# eDP.net
KiCad netlist of a schematic drawn in Altium Designer
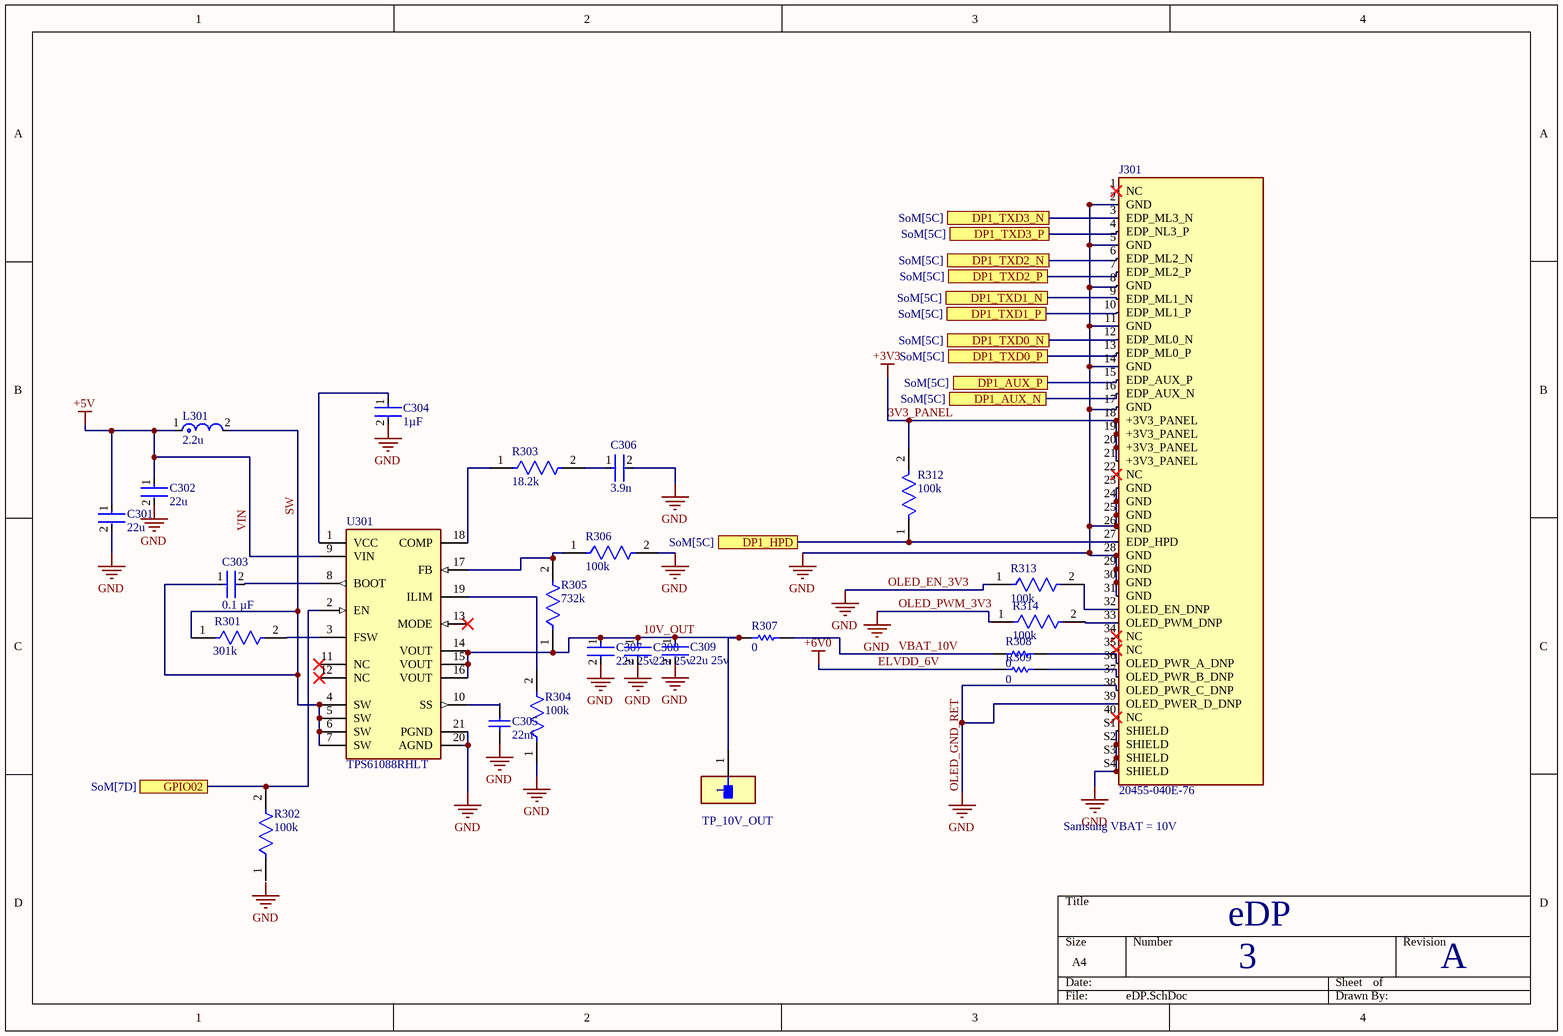
[diagram p0: eDP.SchDoc]

(export (version "E")
  (design (tool "Eeschema 10.0.6"))
  (components
    (comp (ref "C301")
      (value "22u")
      (footprint "FP-CL10-IPC_B")
      (description "Cap Ceramic 22uF 16V X5R ±20% Pad SMD 0603 +85°C T/R")
      (fields (field (name "TOLERANCE") "20%"))
      (libsource (lib "Altium Content Vault") (part "b4654b650e69147ec39a6b967a45e02"))
    )
    (comp (ref "C302")
      (value "22u")
      (footprint "FP-CL10-IPC_B")
      (description "Cap Ceramic 22uF 16V X5R ±20% Pad SMD 0603 +85°C T/R")
      (fields (field (name "TOLERANCE") "20%"))
      (libsource (lib "Altium Content Vault") (part "b4654b650e69147ec39a6b967a45e02"))
    )
    (comp (ref "C303")
      (value "0.1 µF")
      (footprint "FP-GRM155-0_05-IPC_B")
      (description "Chip Multilayer Ceramic Capacitors for General Purpose, 0402, 0.10uF, X7R, 15%, 10%, 50V")
      (fields (field (name "TOLERANCE") "10%"))
      (libsource (lib "Altium Content Vault") (part "02cd4be3c70576c341d710602a673aa"))
    )
    (comp (ref "C304")
      (value "1µF")
      (footprint "FP-GRM15-0_1-MFG")
      (description "CAP CER 1UF 10V X5R 0402")
      (fields
        (field (name "OCTOPART") "https://octopart.com/grm155r61a105ke15d-murata-197442")
        (field (name "MANUFACTURER PART NUMBER") "GRM155R61A105KE15D")
      )
      (libsource (lib "Altium Content Vault") (part "02cd4be3c70576c341d710602a673aa"))
    )
    (comp (ref "C305")
      (value "22nf")
      (footprint "CAPC1608X90X35ML10T15")
      (fields (field (name "MANUFACTURER") "Murata") (field (name "PART NUMBER") "GRM188R71H223KA01D"))
      (libsource (lib "Altium Content Vault") (part "CAP"))
    )
    (comp (ref "C306")
      (value "3.9n")
      (footprint "FP-GRM188-0_1-e0_2_0_5-IPC_B")
      (description "Chip Multilayer Ceramic Capacitors for General Purpose, 0603, 3900pF, C0G, 30ppm/°C, 5%, 50V")
      (fields (field (name "VOLTAGE") "50V") (field (name "TOLERANCE") "5%"))
      (libsource (lib "Altium Content Vault") (part "11868f565c42a9108669ba33697ecf6"))
    )
    (comp (ref "C307")
      (value "22u 25v")
      (footprint "FP-GRM21B-0_2-e0_2_0_7-IPC_B")
      (description "Chip Multilayer Ceramic Capacitors for General Purpose, 0805, 22uF, X5R, 15%, 20%, 25V")
      (fields (field (name "TOLERANCE") "20%") (field (name "VOLTAGE") "25V"))
      (libsource (lib "Altium Content Vault") (part "b4654b650e69147ec39a6b967a45e02"))
    )
    (comp (ref "C308")
      (value "22u 25v")
      (footprint "FP-GRM21B-0_2-e0_2_0_7-IPC_B")
      (description "Chip Multilayer Ceramic Capacitors for General Purpose, 0805, 22uF, X5R, 15%, 20%, 25V")
      (fields (field (name "TOLERANCE") "20%") (field (name "VOLTAGE") "25V"))
      (libsource (lib "Altium Content Vault") (part "b4654b650e69147ec39a6b967a45e02"))
    )
    (comp (ref "C309")
      (value "22u 25v")
      (footprint "FP-GRM21B-0_2-e0_2_0_7-IPC_B")
      (description "Chip Multilayer Ceramic Capacitors for General Purpose, 0805, 22uF, X5R, 15%, 20%, 25V")
      (fields (field (name "TOLERANCE") "20%") (field (name "VOLTAGE") "25V"))
      (libsource (lib "Altium Content Vault") (part "b4654b650e69147ec39a6b967a45e02"))
    )
    (comp (ref "J300")
      (value "TP_10V_OUT")
      (footprint "FP-S2751-46R-MFG")
      (description "10V nominal")
      (libsource (lib "Altium Content Vault") (part "dd45045ce8184df9e99e12baf3f412c"))
    )
    (comp (ref "J301")
      (value "20455-040E-76")
      (footprint "IPEX_20455-040E-76")
      (description "Conn Wire to Board RCP 40 POS 0.5mm Solder RA Side Entry SMDCABLINE® T/R")
      (libsource (lib "Evan") (part "20455-040E-76"))
    )
    (comp (ref "L301")
      (value "2.2u")
      (footprint "FP-XAL5030-222MEC-MFG")
      (description "Fixed Inductors 2.2uH Shld 20% 9.2A 14.5mOhms AECQ2 SRF: 38MHz Test Freq: 1MHz")
      (fields (field (name "TOLERANCE") "20%"))
      (libsource (lib "Altium Content Vault") (part "4cc4b267dca4c8e51f7102f422741d8"))
    )
    (comp (ref "R301")
      (value "301k")
      (footprint "FP-CRCW0603-e3-IPC_C")
      (description "RES Thick Film, 301kΩ, 1%, 0.1W, 100ppm/°C, 0603")
      (fields (field (name "TOLERANCE") "1%"))
      (libsource (lib "Altium Content Vault") (part "1029c3af85768c4190bb7ad29bc67b5"))
    )
    (comp (ref "R302")
      (value "100k")
      (footprint "FP-CRCW0603C-e3-MFG")
      (description "RES SMD 100K OHM 1% 1/10W 0603")
      (fields (field (name "TOLERANCE") "1%"))
      (libsource (lib "Altium Content Vault") (part "1029c3af85768c4190bb7ad29bc67b5"))
    )
    (comp (ref "R303")
      (value "18.2k")
      (footprint "FP-CRCW0603-e3-IPC_C")
      (description "RES Thick Film, 18.2kΩ, 1%, 0.1W, 100ppm/°C, 0603")
      (fields (field (name "TOLERANCE") "1%"))
      (libsource (lib "Altium Content Vault") (part "1029c3af85768c4190bb7ad29bc67b5"))
    )
    (comp (ref "R304")
      (value "100k")
      (footprint "FP-CRCW0603C-e3-MFG")
      (description "RES SMD 100K OHM 1% 1/10W 0603")
      (fields (field (name "TOLERANCE") "1%"))
      (libsource (lib "Altium Content Vault") (part "1029c3af85768c4190bb7ad29bc67b5"))
    )
    (comp (ref "R305")
      (value "732k")
      (footprint "FP-CRCW0603-e3-IPC_B")
      (description "RES Thick Film, 732kΩ, 1%, 0.1W, 100ppm/°C, 0603")
      (fields (field (name "TOLERANCE") "1%"))
      (libsource (lib "Altium Content Vault") (part "1029c3af85768c4190bb7ad29bc67b5"))
    )
    (comp (ref "R306")
      (value "100k")
      (footprint "FP-CRCW0603C-e3-MFG")
      (description "RES SMD 100K OHM 1% 1/10W 0603")
      (fields (field (name "TOLERANCE") "1%"))
      (libsource (lib "Altium Content Vault") (part "1029c3af85768c4190bb7ad29bc67b5"))
    )
    (comp (ref "R307")
      (value "0")
      (footprint "RESC1005X40X25NL05T10")
      (fields (field (name "MANUFACTURER") "Yageo / Phycomp") (field (name "PART NUMBER") "RC0402JR-070RL"))
      (libsource (lib "Altium Content Vault") (part "RES"))
    )
    (comp (ref "R308")
      (value "0")
      (footprint "RESC1005X40X25NL05T10")
      (fields (field (name "MANUFACTURER") "Yageo / Phycomp") (field (name "PART NUMBER") "RC0402JR-070RL"))
      (libsource (lib "Altium Content Vault") (part "RES"))
    )
    (comp (ref "R309")
      (value "0")
      (footprint "RESC1005X40X25NL05T10")
      (fields (field (name "MANUFACTURER") "Yageo / Phycomp") (field (name "PART NUMBER") "RC0402JR-070RL"))
      (libsource (lib "Altium Content Vault") (part "RES"))
    )
    (comp (ref "R312")
      (value "100k")
      (footprint "FP-RC0402-0_4-IPC_A")
      (description "RES 100K OHM 5% 1/16W 0402")
      (fields (field (name "TOLERANCE") "5%"))
      (libsource (lib "Altium Content Vault") (part "1029c3af85768c4190bb7ad29bc67b5"))
    )
    (comp (ref "R313")
      (value "100k")
      (footprint "FP-CRCW0603C-e3-MFG")
      (description "RES SMD 100K OHM 1% 1/10W 0603")
      (fields (field (name "TOLERANCE") "1%"))
      (libsource (lib "Altium Content Vault") (part "1029c3af85768c4190bb7ad29bc67b5"))
    )
    (comp (ref "R314")
      (value "100k")
      (footprint "FP-CRCW0603C-e3-MFG")
      (description "RES SMD 100K OHM 1% 1/10W 0603")
      (fields (field (name "TOLERANCE") "1%"))
      (libsource (lib "Altium Content Vault") (part "1029c3af85768c4190bb7ad29bc67b5"))
    )
    (comp (ref "U301")
      (value "TPS61088RHLT")
      (footprint "FP-RHL0020A-MFG")
      (description "IC REG BOOST ADJ 10A 20VQFN")
      (fields
        (field (name "OCTOPART") "https://octopart.com/tps61088rhlt-texas+instruments-57155059")
        (field (name "MANUFACTURER") "Texas Instruments")
      )
      (libsource (lib "Altium Content Vault") (part "866d791168d43c93e8e886550da2fd8"))
    )
  )
  (nets
    (net (code "1") (name "+3V3") (class "Default")
      (node (ref "J301") (pin "18") (pinfunction "+3V3_PANEL_18") (pintype "passive"))
      (node (ref "J301") (pin "19") (pinfunction "+3V3_PANEL_19") (pintype "passive"))
      (node (ref "J301") (pin "20") (pinfunction "+3V3_PANEL_20") (pintype "passive"))
      (node (ref "J301") (pin "21") (pinfunction "+3V3_PANEL_21") (pintype "passive"))
      (node (ref "R312") (pin "2") (pinfunction "2_2") (pintype "passive"))
    )
    (net (code "2") (name "+5V") (class "Default")
      (node (ref "C301") (pin "1") (pinfunction "1_1") (pintype "passive"))
      (node (ref "C302") (pin "1") (pinfunction "1_1") (pintype "passive"))
      (node (ref "L301") (pin "1") (pinfunction "1_1") (pintype "passive"))
      (node (ref "U301") (pin "9") (pinfunction "VIN_9") (pintype "power_in"))
    )
    (net (code "3") (name "+6V0") (class "Default")
      (node (ref "R309") (pin "1") (pinfunction "1_1") (pintype "passive"))
    )
    (net (code "4") (name "/10V_OUT") (class "Default")
      (node (ref "C307") (pin "1") (pinfunction "1_1") (pintype "passive"))
      (node (ref "C308") (pin "1") (pinfunction "1_1") (pintype "passive"))
      (node (ref "C309") (pin "1") (pinfunction "1_1") (pintype "passive"))
      (node (ref "J300") (pin "1") (pinfunction "1_1") (pintype "passive"))
      (node (ref "R305") (pin "1") (pinfunction "1_1") (pintype "passive"))
      (node (ref "R307") (pin "1") (pinfunction "1_1") (pintype "passive"))
      (node (ref "U301") (pin "14") (pinfunction "VOUT_14") (pintype "power_in"))
      (node (ref "U301") (pin "15") (pinfunction "VOUT_15") (pintype "power_in"))
      (node (ref "U301") (pin "16") (pinfunction "VOUT_16") (pintype "power_in"))
    )
    (net (code "5") (name "/DP1_AUX_N") (class "Default")
      (node (ref "J301") (pin "16") (pinfunction "EDP_AUX_N_16") (pintype "passive"))
    )
    (net (code "6") (name "/DP1_AUX_P") (class "Default")
      (node (ref "J301") (pin "15") (pinfunction "EDP_AUX_P_15") (pintype "passive"))
    )
    (net (code "7") (name "/DP1_HPD") (class "Default")
      (node (ref "J301") (pin "27") (pinfunction "EDP_HPD_27") (pintype "passive"))
      (node (ref "R312") (pin "1") (pinfunction "1_1") (pintype "passive"))
    )
    (net (code "8") (name "/DP1_TXD0_N") (class "Default")
      (node (ref "J301") (pin "12") (pinfunction "EDP_ML0_N_12") (pintype "passive"))
    )
    (net (code "9") (name "/DP1_TXD0_P") (class "Default")
      (node (ref "J301") (pin "13") (pinfunction "EDP_ML0_P_13") (pintype "passive"))
    )
    (net (code "10") (name "/DP1_TXD1_N") (class "Default")
      (node (ref "J301") (pin "9") (pinfunction "EDP_ML1_N_9") (pintype "passive"))
    )
    (net (code "11") (name "/DP1_TXD1_P") (class "Default")
      (node (ref "J301") (pin "10") (pinfunction "EDP_ML1_P_10") (pintype "passive"))
    )
    (net (code "12") (name "/DP1_TXD2_N") (class "Default")
      (node (ref "J301") (pin "6") (pinfunction "EDP_ML2_N_6") (pintype "passive"))
    )
    (net (code "13") (name "/DP1_TXD2_P") (class "Default")
      (node (ref "J301") (pin "7") (pinfunction "EDP_ML2_P_7") (pintype "passive"))
    )
    (net (code "14") (name "/DP1_TXD3_N") (class "Default")
      (node (ref "J301") (pin "3") (pinfunction "EDP_ML3_N_3") (pintype "passive"))
    )
    (net (code "15") (name "/DP1_TXD3_P") (class "Default")
      (node (ref "J301") (pin "4") (pinfunction "EDP_NL3_P_4") (pintype "passive"))
    )
    (net (code "16") (name "/GPIO02") (class "Default")
      (node (ref "R302") (pin "2") (pinfunction "2_2") (pintype "passive"))
      (node (ref "U301") (pin "2") (pinfunction "EN_2") (pintype "input"))
    )
    (net (code "17") (name "/SW") (class "Default")
      (node (ref "C303") (pin "1") (pinfunction "1_1") (pintype "passive"))
      (node (ref "L301") (pin "2") (pinfunction "2_2") (pintype "passive"))
      (node (ref "R301") (pin "1") (pinfunction "1_1") (pintype "passive"))
      (node (ref "U301") (pin "4") (pinfunction "SW_4") (pintype "power_in"))
      (node (ref "U301") (pin "5") (pinfunction "SW_5") (pintype "power_in"))
      (node (ref "U301") (pin "6") (pinfunction "SW_6") (pintype "power_in"))
      (node (ref "U301") (pin "7") (pinfunction "SW_7") (pintype "power_in"))
    )
    (net (code "18") (name "/VBAT_10V") (class "Default")
      (node (ref "R307") (pin "2") (pinfunction "2_2") (pintype "passive"))
      (node (ref "R308") (pin "1") (pinfunction "1_1") (pintype "passive"))
    )
    (net (code "19") (name "GND") (class "Default")
      (node (ref "C301") (pin "2") (pinfunction "2_2") (pintype "passive"))
      (node (ref "C302") (pin "2") (pinfunction "2_2") (pintype "passive"))
      (node (ref "C304") (pin "2") (pinfunction "2_2") (pintype "passive"))
      (node (ref "C305") (pin "1") (pinfunction "1_1") (pintype "passive"))
      (node (ref "C306") (pin "2") (pinfunction "2_2") (pintype "passive"))
      (node (ref "C307") (pin "2") (pinfunction "2_2") (pintype "passive"))
      (node (ref "C308") (pin "2") (pinfunction "2_2") (pintype "passive"))
      (node (ref "C309") (pin "2") (pinfunction "2_2") (pintype "passive"))
      (node (ref "J301") (pin "11") (pinfunction "GND_11") (pintype "passive"))
      (node (ref "J301") (pin "14") (pinfunction "GND_14") (pintype "passive"))
      (node (ref "J301") (pin "17") (pinfunction "GND_17") (pintype "passive"))
      (node (ref "J301") (pin "2") (pinfunction "GND_2") (pintype "passive"))
      (node (ref "J301") (pin "23") (pinfunction "GND_23") (pintype "passive"))
      (node (ref "J301") (pin "24") (pinfunction "GND_24") (pintype "passive"))
      (node (ref "J301") (pin "25") (pinfunction "GND_25") (pintype "passive"))
      (node (ref "J301") (pin "26") (pinfunction "GND_26") (pintype "passive"))
      (node (ref "J301") (pin "28") (pinfunction "GND_28") (pintype "passive"))
      (node (ref "J301") (pin "29") (pinfunction "GND_29") (pintype "passive"))
      (node (ref "J301") (pin "30") (pinfunction "GND_30") (pintype "passive"))
      (node (ref "J301") (pin "31") (pinfunction "GND_31") (pintype "passive"))
      (node (ref "J301") (pin "38") (pinfunction "OLED_PWR_C_DNP_38") (pintype "passive"))
      (node (ref "J301") (pin "39") (pinfunction "OLED_PWER_D_DNP_39") (pintype "passive"))
      (node (ref "J301") (pin "5") (pinfunction "GND_5") (pintype "passive"))
      (node (ref "J301") (pin "8") (pinfunction "GND_8") (pintype "passive"))
      (node (ref "J301") (pin "S1") (pinfunction "SHIELD_S1") (pintype "passive"))
      (node (ref "J301") (pin "S2") (pinfunction "SHIELD_S2") (pintype "passive"))
      (node (ref "J301") (pin "S3") (pinfunction "SHIELD_S3") (pintype "passive"))
      (node (ref "J301") (pin "S4") (pinfunction "SHIELD_S4") (pintype "passive"))
      (node (ref "R304") (pin "1") (pinfunction "1_1") (pintype "passive"))
      (node (ref "R306") (pin "2") (pinfunction "2_2") (pintype "passive"))
      (node (ref "R313") (pin "1") (pinfunction "1_1") (pintype "passive"))
      (node (ref "R314") (pin "1") (pinfunction "1_1") (pintype "passive"))
      (node (ref "U301") (pin "20") (pinfunction "AGND_20") (pintype "power_in"))
      (node (ref "U301") (pin "21") (pinfunction "PGND_21") (pintype "power_in"))
    )
    (net (code "20") (name "Net-(C306-Pad1)") (class "Default")
      (node (ref "C306") (pin "1") (pinfunction "1_1") (pintype "passive"))
      (node (ref "R303") (pin "2") (pinfunction "2_2") (pintype "passive"))
    )
    (net (code "21") (name "Net-(J301-OLED_EN_DNP)") (class "Default")
      (node (ref "J301") (pin "32") (pinfunction "OLED_EN_DNP_32") (pintype "passive"))
      (node (ref "R313") (pin "2") (pinfunction "2_2") (pintype "passive"))
    )
    (net (code "22") (name "Net-(J301-OLED_PWM_DNP)") (class "Default")
      (node (ref "J301") (pin "33") (pinfunction "OLED_PWM_DNP_33") (pintype "passive"))
      (node (ref "R314") (pin "2") (pinfunction "2_2") (pintype "passive"))
    )
    (net (code "23") (name "Net-(J301-OLED_PWR_A_DNP)") (class "Default")
      (node (ref "J301") (pin "36") (pinfunction "OLED_PWR_A_DNP_36") (pintype "passive"))
      (node (ref "R308") (pin "2") (pinfunction "2_2") (pintype "passive"))
    )
    (net (code "24") (name "Net-(J301-OLED_PWR_B_DNP)") (class "Default")
      (node (ref "J301") (pin "37") (pinfunction "OLED_PWR_B_DNP_37") (pintype "passive"))
      (node (ref "R309") (pin "2") (pinfunction "2_2") (pintype "passive"))
    )
    (net (code "25") (name "Net-(U301-BOOT)") (class "Default")
      (node (ref "C303") (pin "2") (pinfunction "2_2") (pintype "passive"))
      (node (ref "U301") (pin "8") (pinfunction "BOOT_8") (pintype "output"))
    )
    (net (code "26") (name "Net-(U301-COMP)") (class "Default")
      (node (ref "R303") (pin "1") (pinfunction "1_1") (pintype "passive"))
      (node (ref "U301") (pin "18") (pinfunction "COMP_18") (pintype "passive"))
    )
    (net (code "27") (name "Net-(U301-FB)") (class "Default")
      (node (ref "R305") (pin "2") (pinfunction "2_2") (pintype "passive"))
      (node (ref "R306") (pin "1") (pinfunction "1_1") (pintype "passive"))
      (node (ref "U301") (pin "17") (pinfunction "FB_17") (pintype "input"))
    )
    (net (code "28") (name "Net-(U301-FSW)") (class "Default")
      (node (ref "R301") (pin "2") (pinfunction "2_2") (pintype "passive"))
      (node (ref "U301") (pin "3") (pinfunction "FSW_3") (pintype "passive"))
    )
    (net (code "29") (name "Net-(U301-ILIM)") (class "Default")
      (node (ref "R304") (pin "2") (pinfunction "2_2") (pintype "passive"))
      (node (ref "U301") (pin "19") (pinfunction "ILIM_19") (pintype "passive"))
    )
    (net (code "30") (name "Net-(U301-SS)") (class "Default")
      (node (ref "C305") (pin "2") (pinfunction "2_2") (pintype "passive"))
      (node (ref "U301") (pin "10") (pinfunction "SS_10") (pintype "output"))
    )
    (net (code "31") (name "Net-(U301-VCC)") (class "Default")
      (node (ref "C304") (pin "1") (pinfunction "1_1") (pintype "passive"))
      (node (ref "U301") (pin "1") (pinfunction "VCC_1") (pintype "power_in"))
    )
    (net (code "32") (name "unconnected-(J301-NC-Pad1)") (class "Default")
      (node (ref "J301") (pin "1") (pinfunction "NC_1") (pintype "passive+no_connect"))
    )
    (net (code "33") (name "unconnected-(J301-NC-Pad22)") (class "Default")
      (node (ref "J301") (pin "22") (pinfunction "NC_22") (pintype "passive+no_connect"))
    )
    (net (code "34") (name "unconnected-(J301-NC-Pad34)") (class "Default")
      (node (ref "J301") (pin "34") (pinfunction "NC_34") (pintype "passive+no_connect"))
    )
    (net (code "35") (name "unconnected-(J301-NC-Pad35)") (class "Default")
      (node (ref "J301") (pin "35") (pinfunction "NC_35") (pintype "passive+no_connect"))
    )
    (net (code "36") (name "unconnected-(J301-NC-Pad40)") (class "Default")
      (node (ref "J301") (pin "40") (pinfunction "NC_40") (pintype "passive+no_connect"))
    )
    (net (code "37") (name "unconnected-(R302-Pad1)") (class "Default")
      (node (ref "R302") (pin "1") (pinfunction "1_1") (pintype "passive"))
    )
    (net (code "38") (name "unconnected-(U301-MODE-Pad13)") (class "Default")
      (node (ref "U301") (pin "13") (pinfunction "MODE_13") (pintype "input+no_connect"))
    )
    (net (code "39") (name "unconnected-(U301-NC-Pad11)") (class "Default")
      (node (ref "U301") (pin "11") (pinfunction "NC_11") (pintype "passive+no_connect"))
    )
    (net (code "40") (name "unconnected-(U301-NC-Pad12)") (class "Default")
      (node (ref "U301") (pin "12") (pinfunction "NC_12") (pintype "passive+no_connect"))
    )
  )
)
